# Electronics_Sensor_Modules.net
KiCad netlist of a schematic drawn in EasyEDA
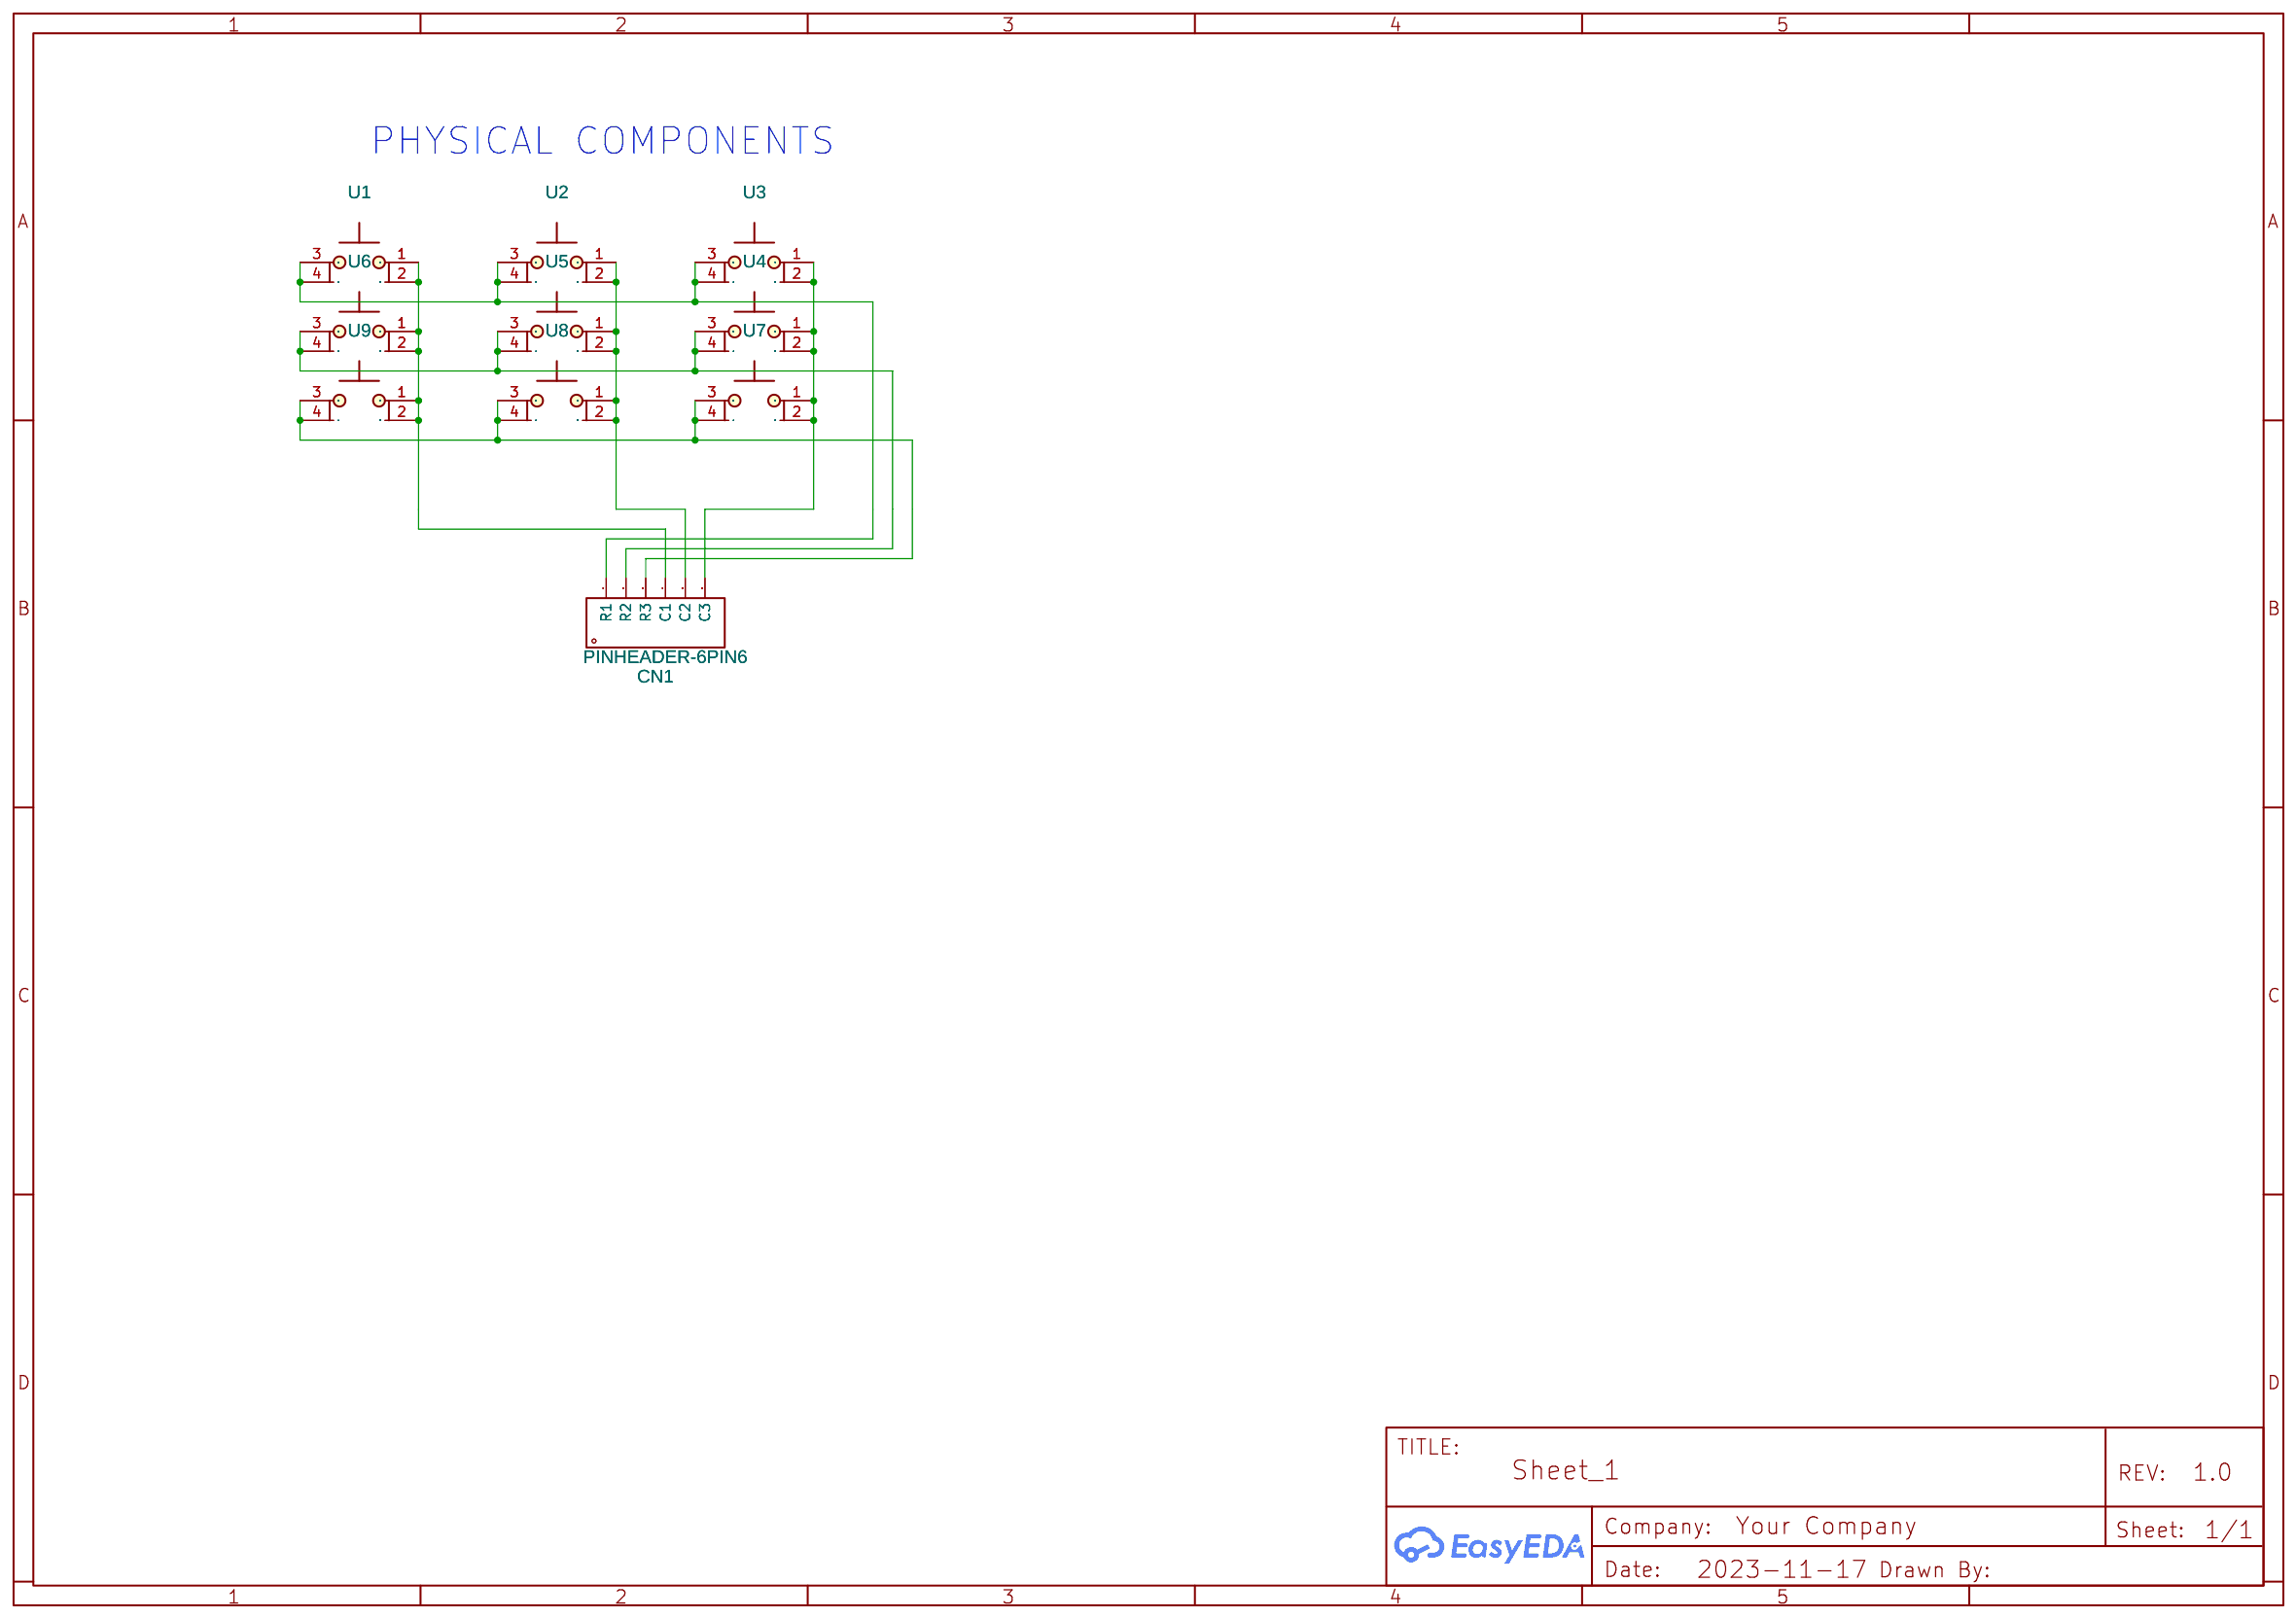
[diagram p0: 3x3 KeyPad]
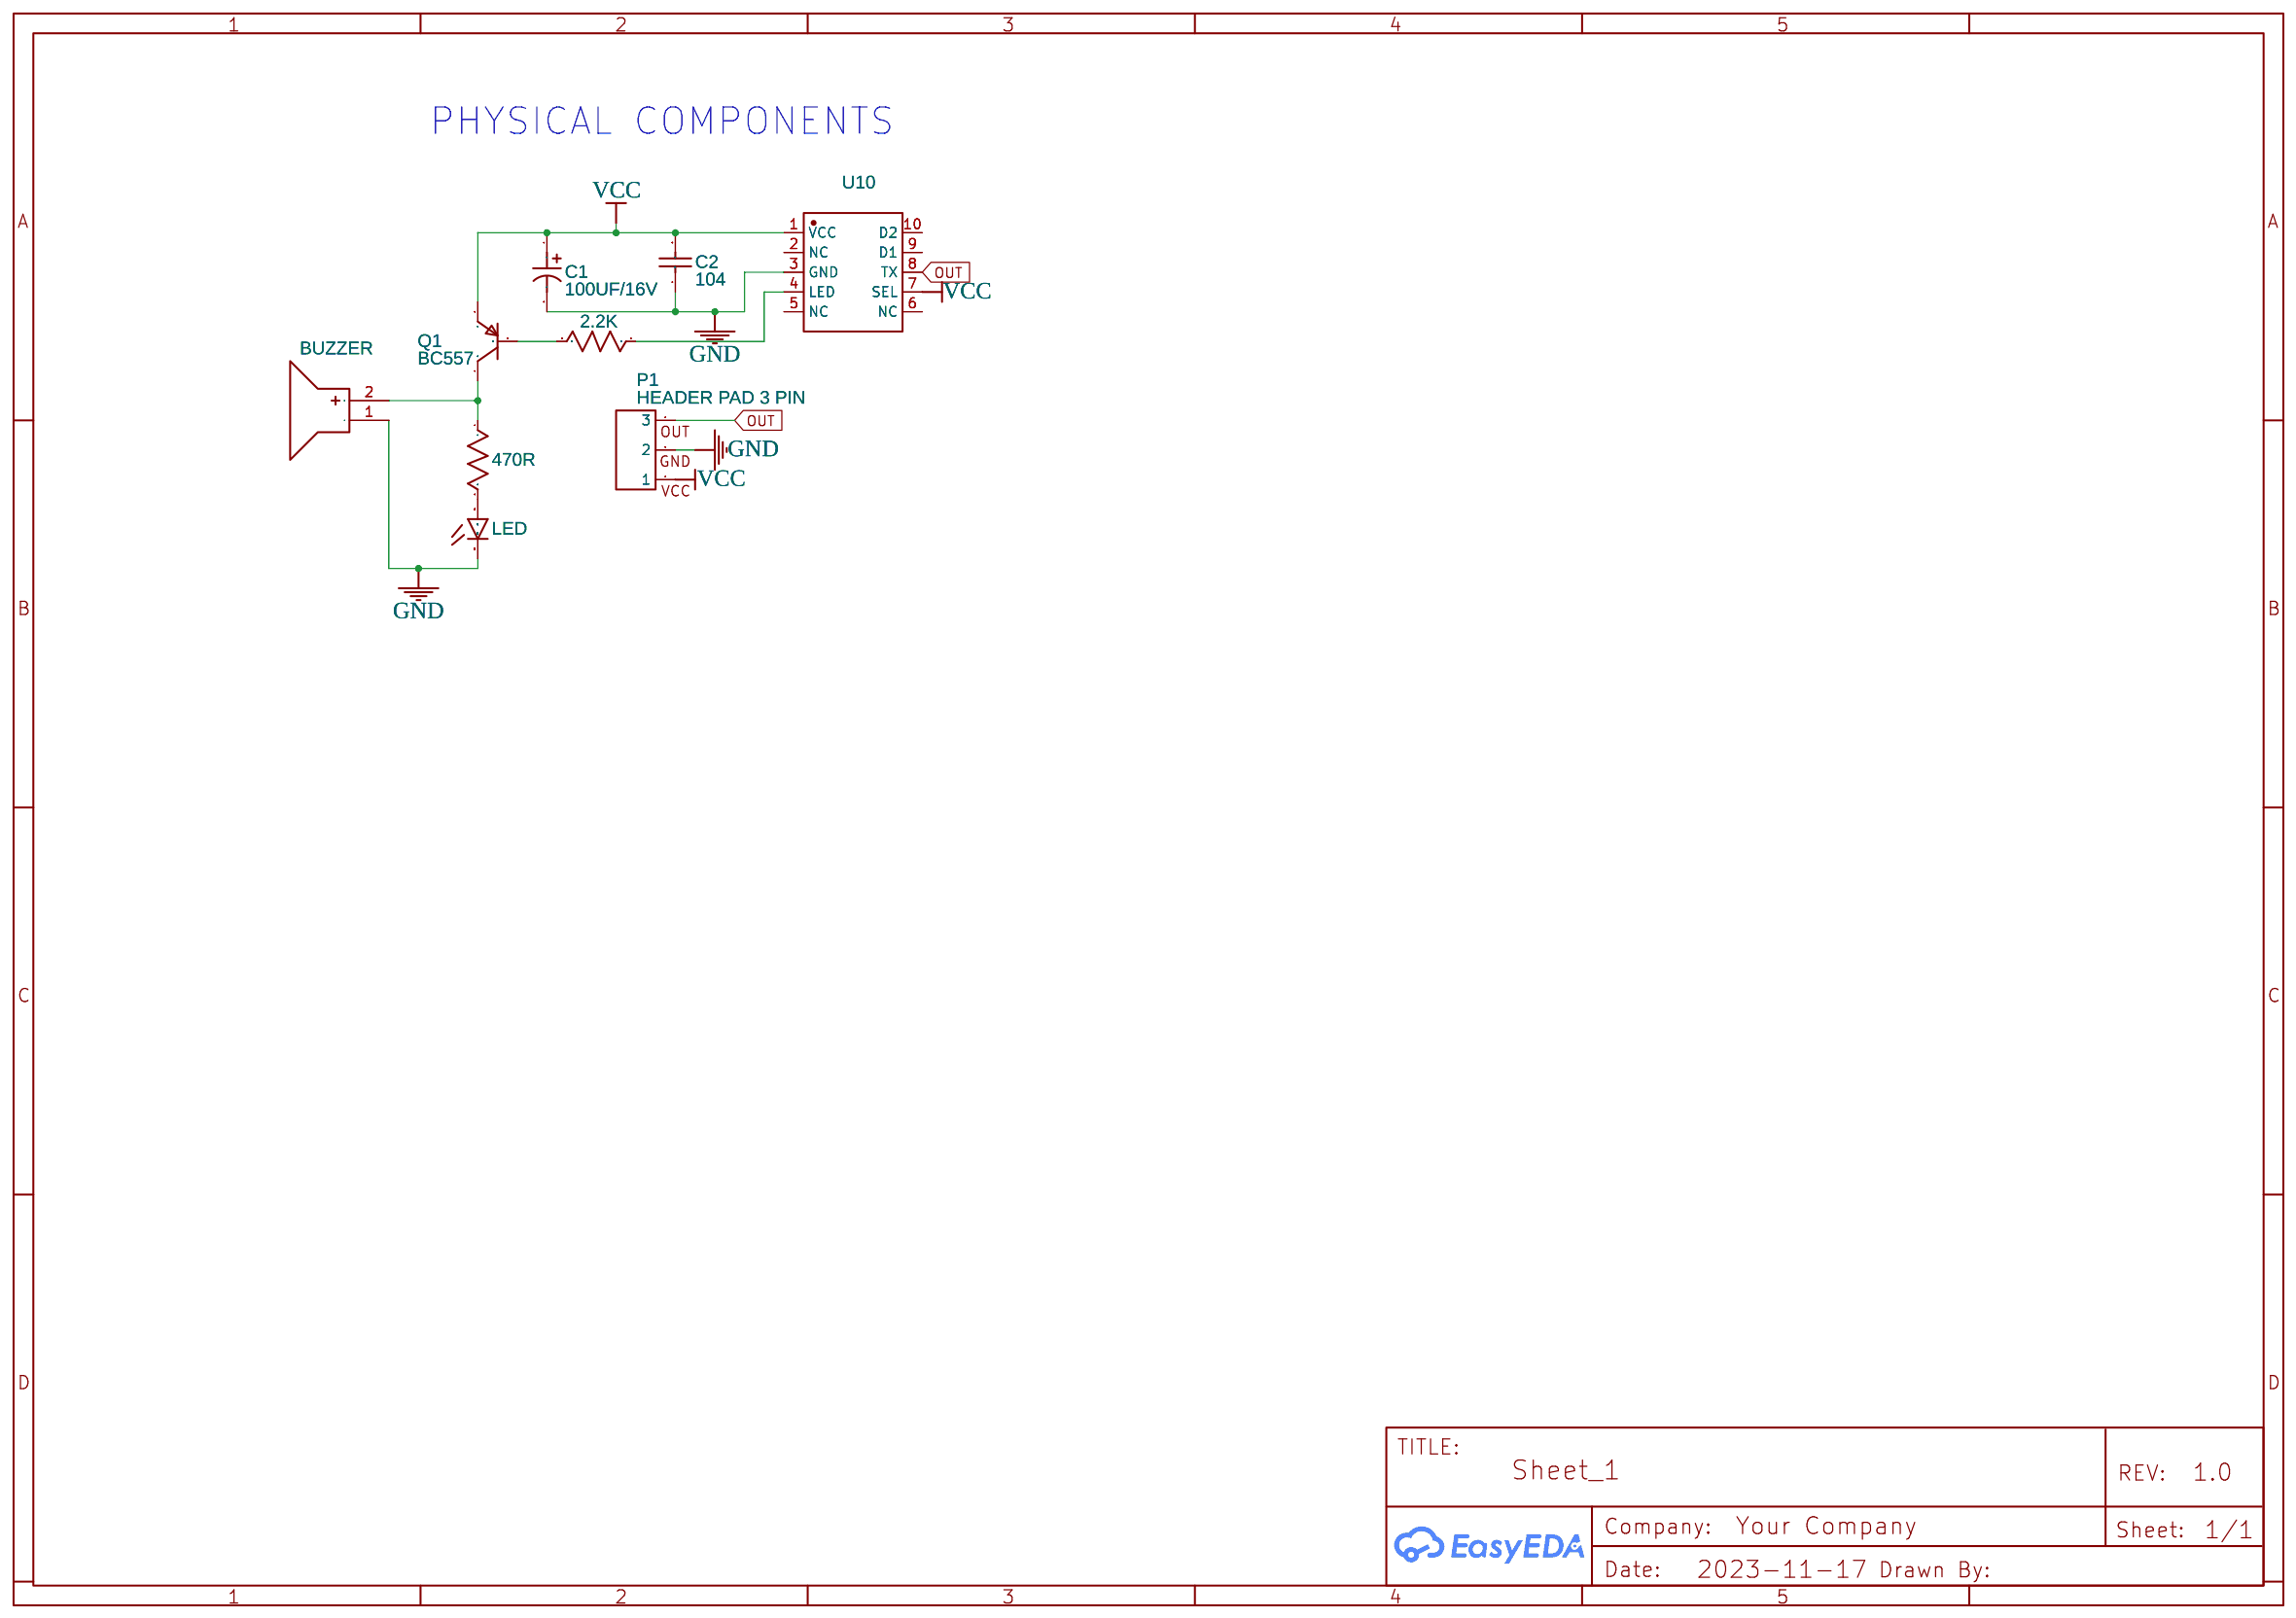
[diagram p1: EM-18 Module]
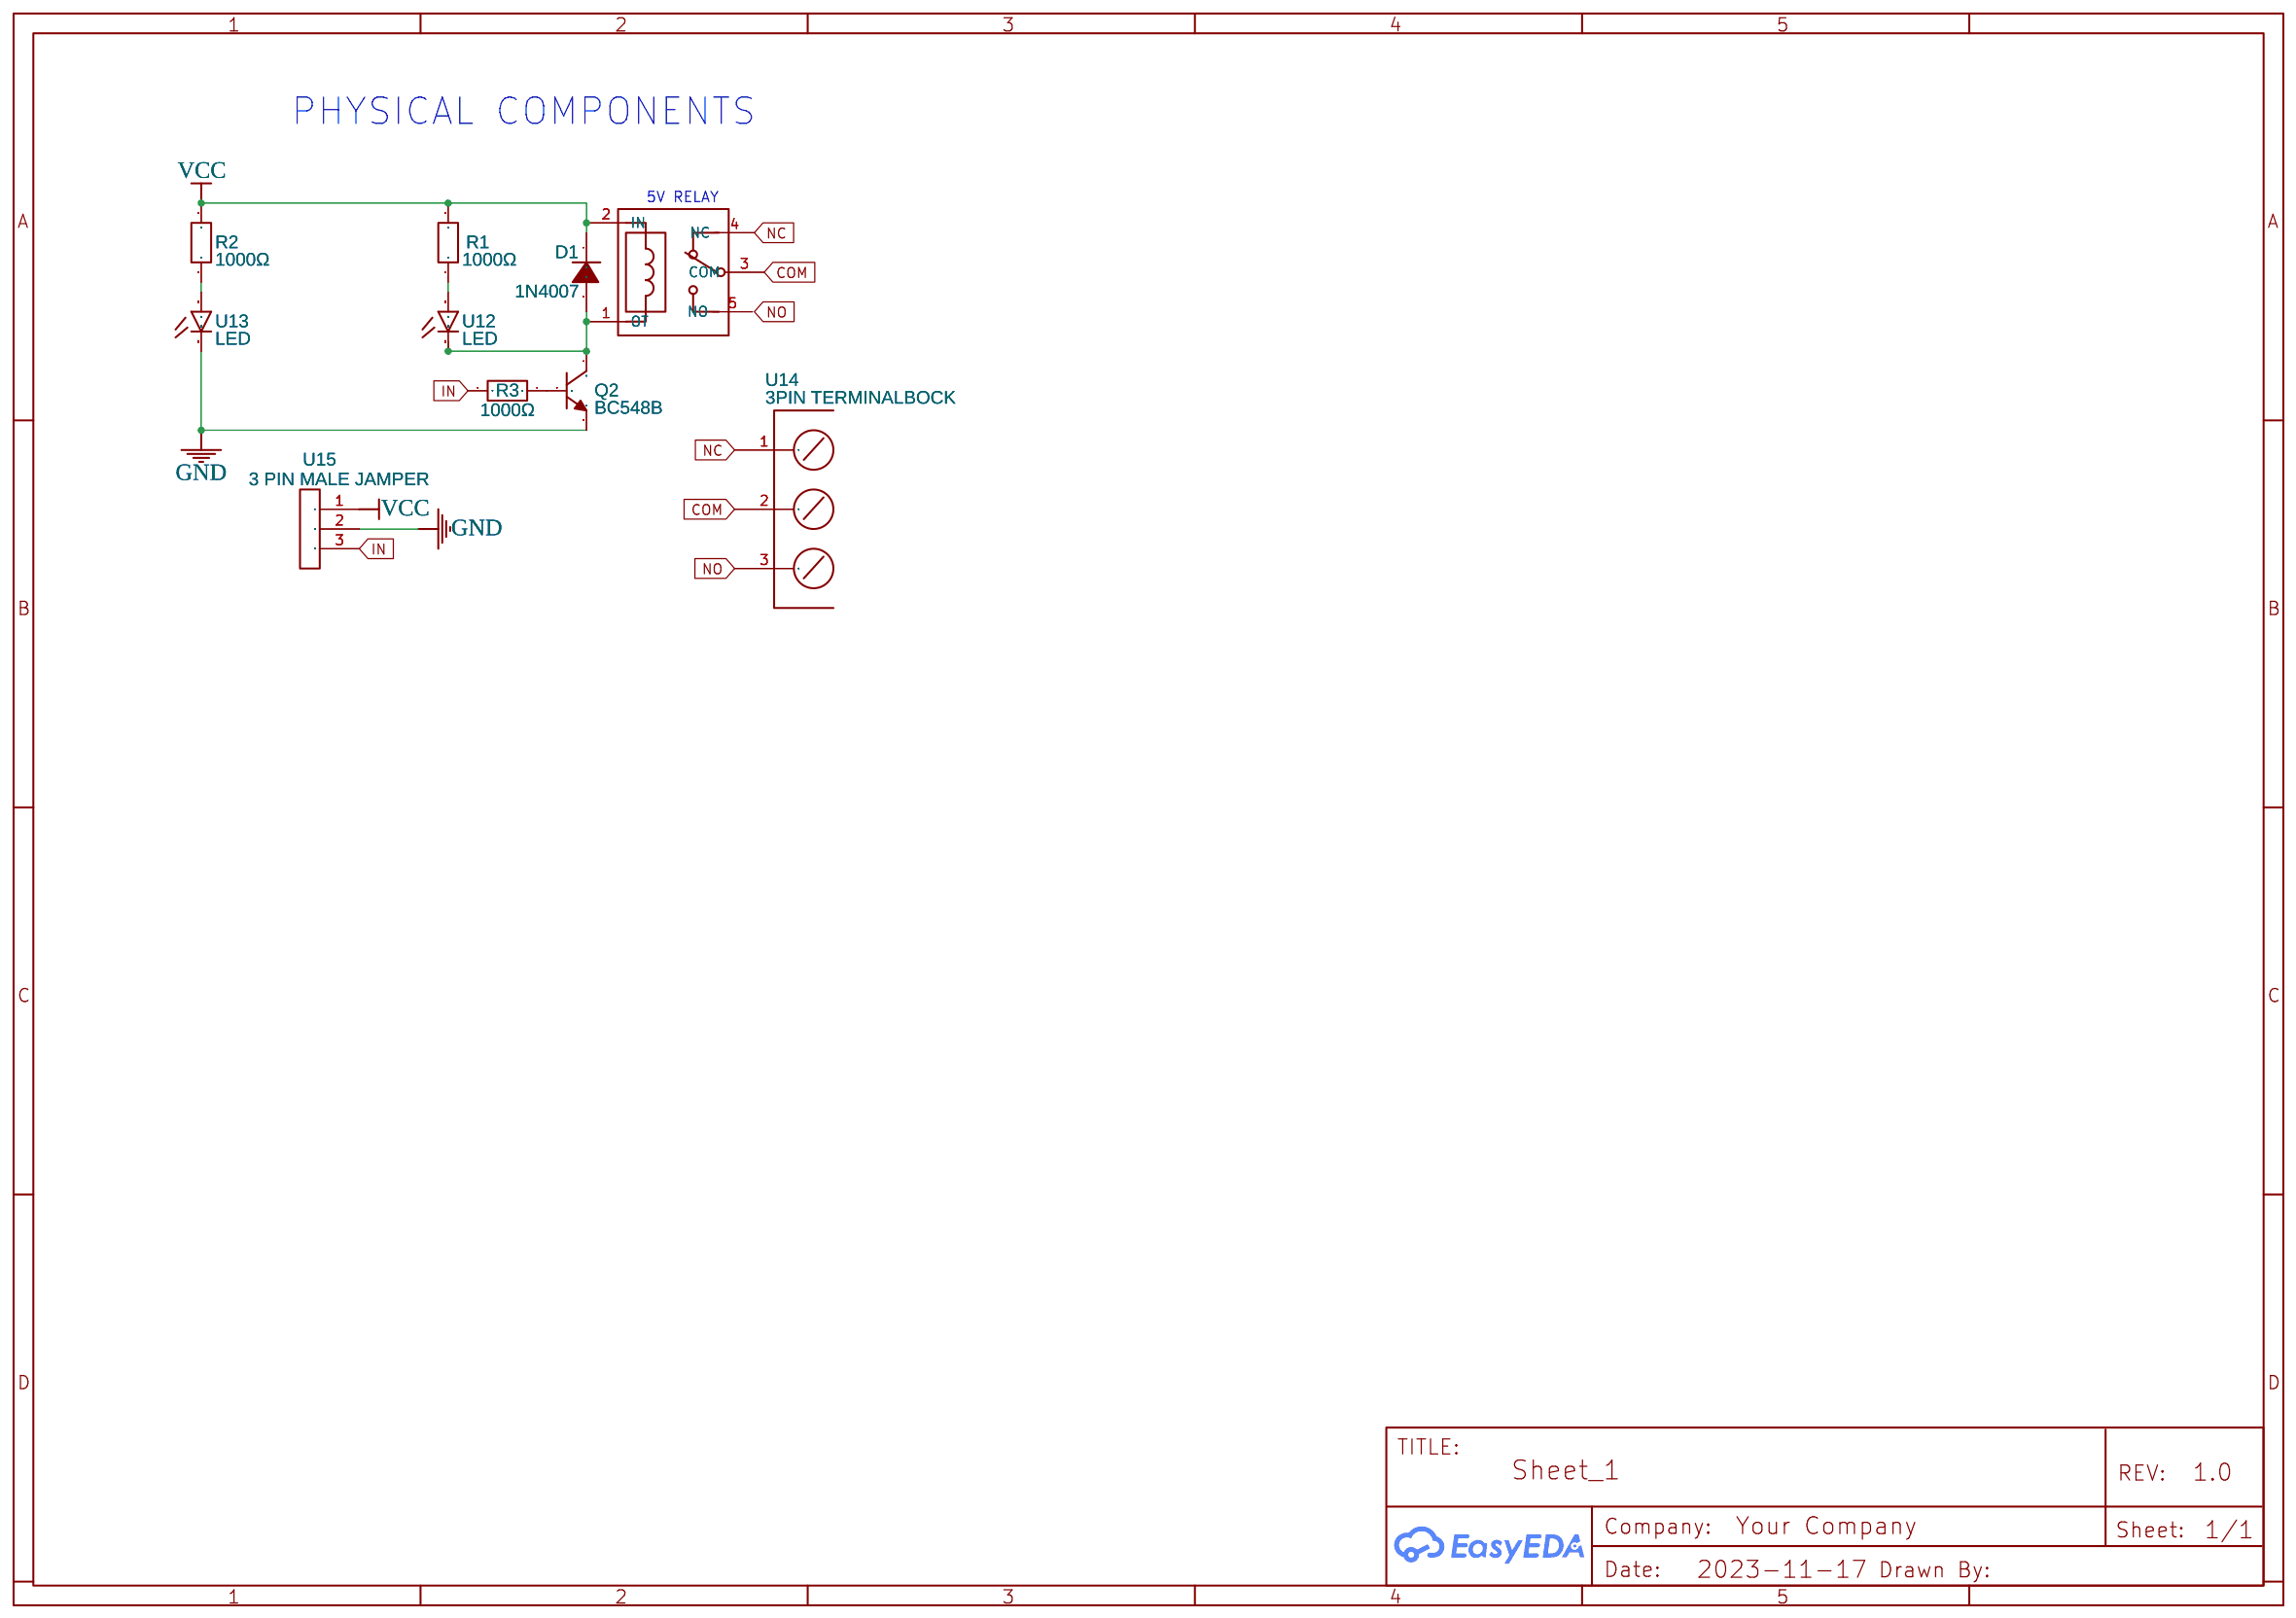
[diagram p2: Relay Module]
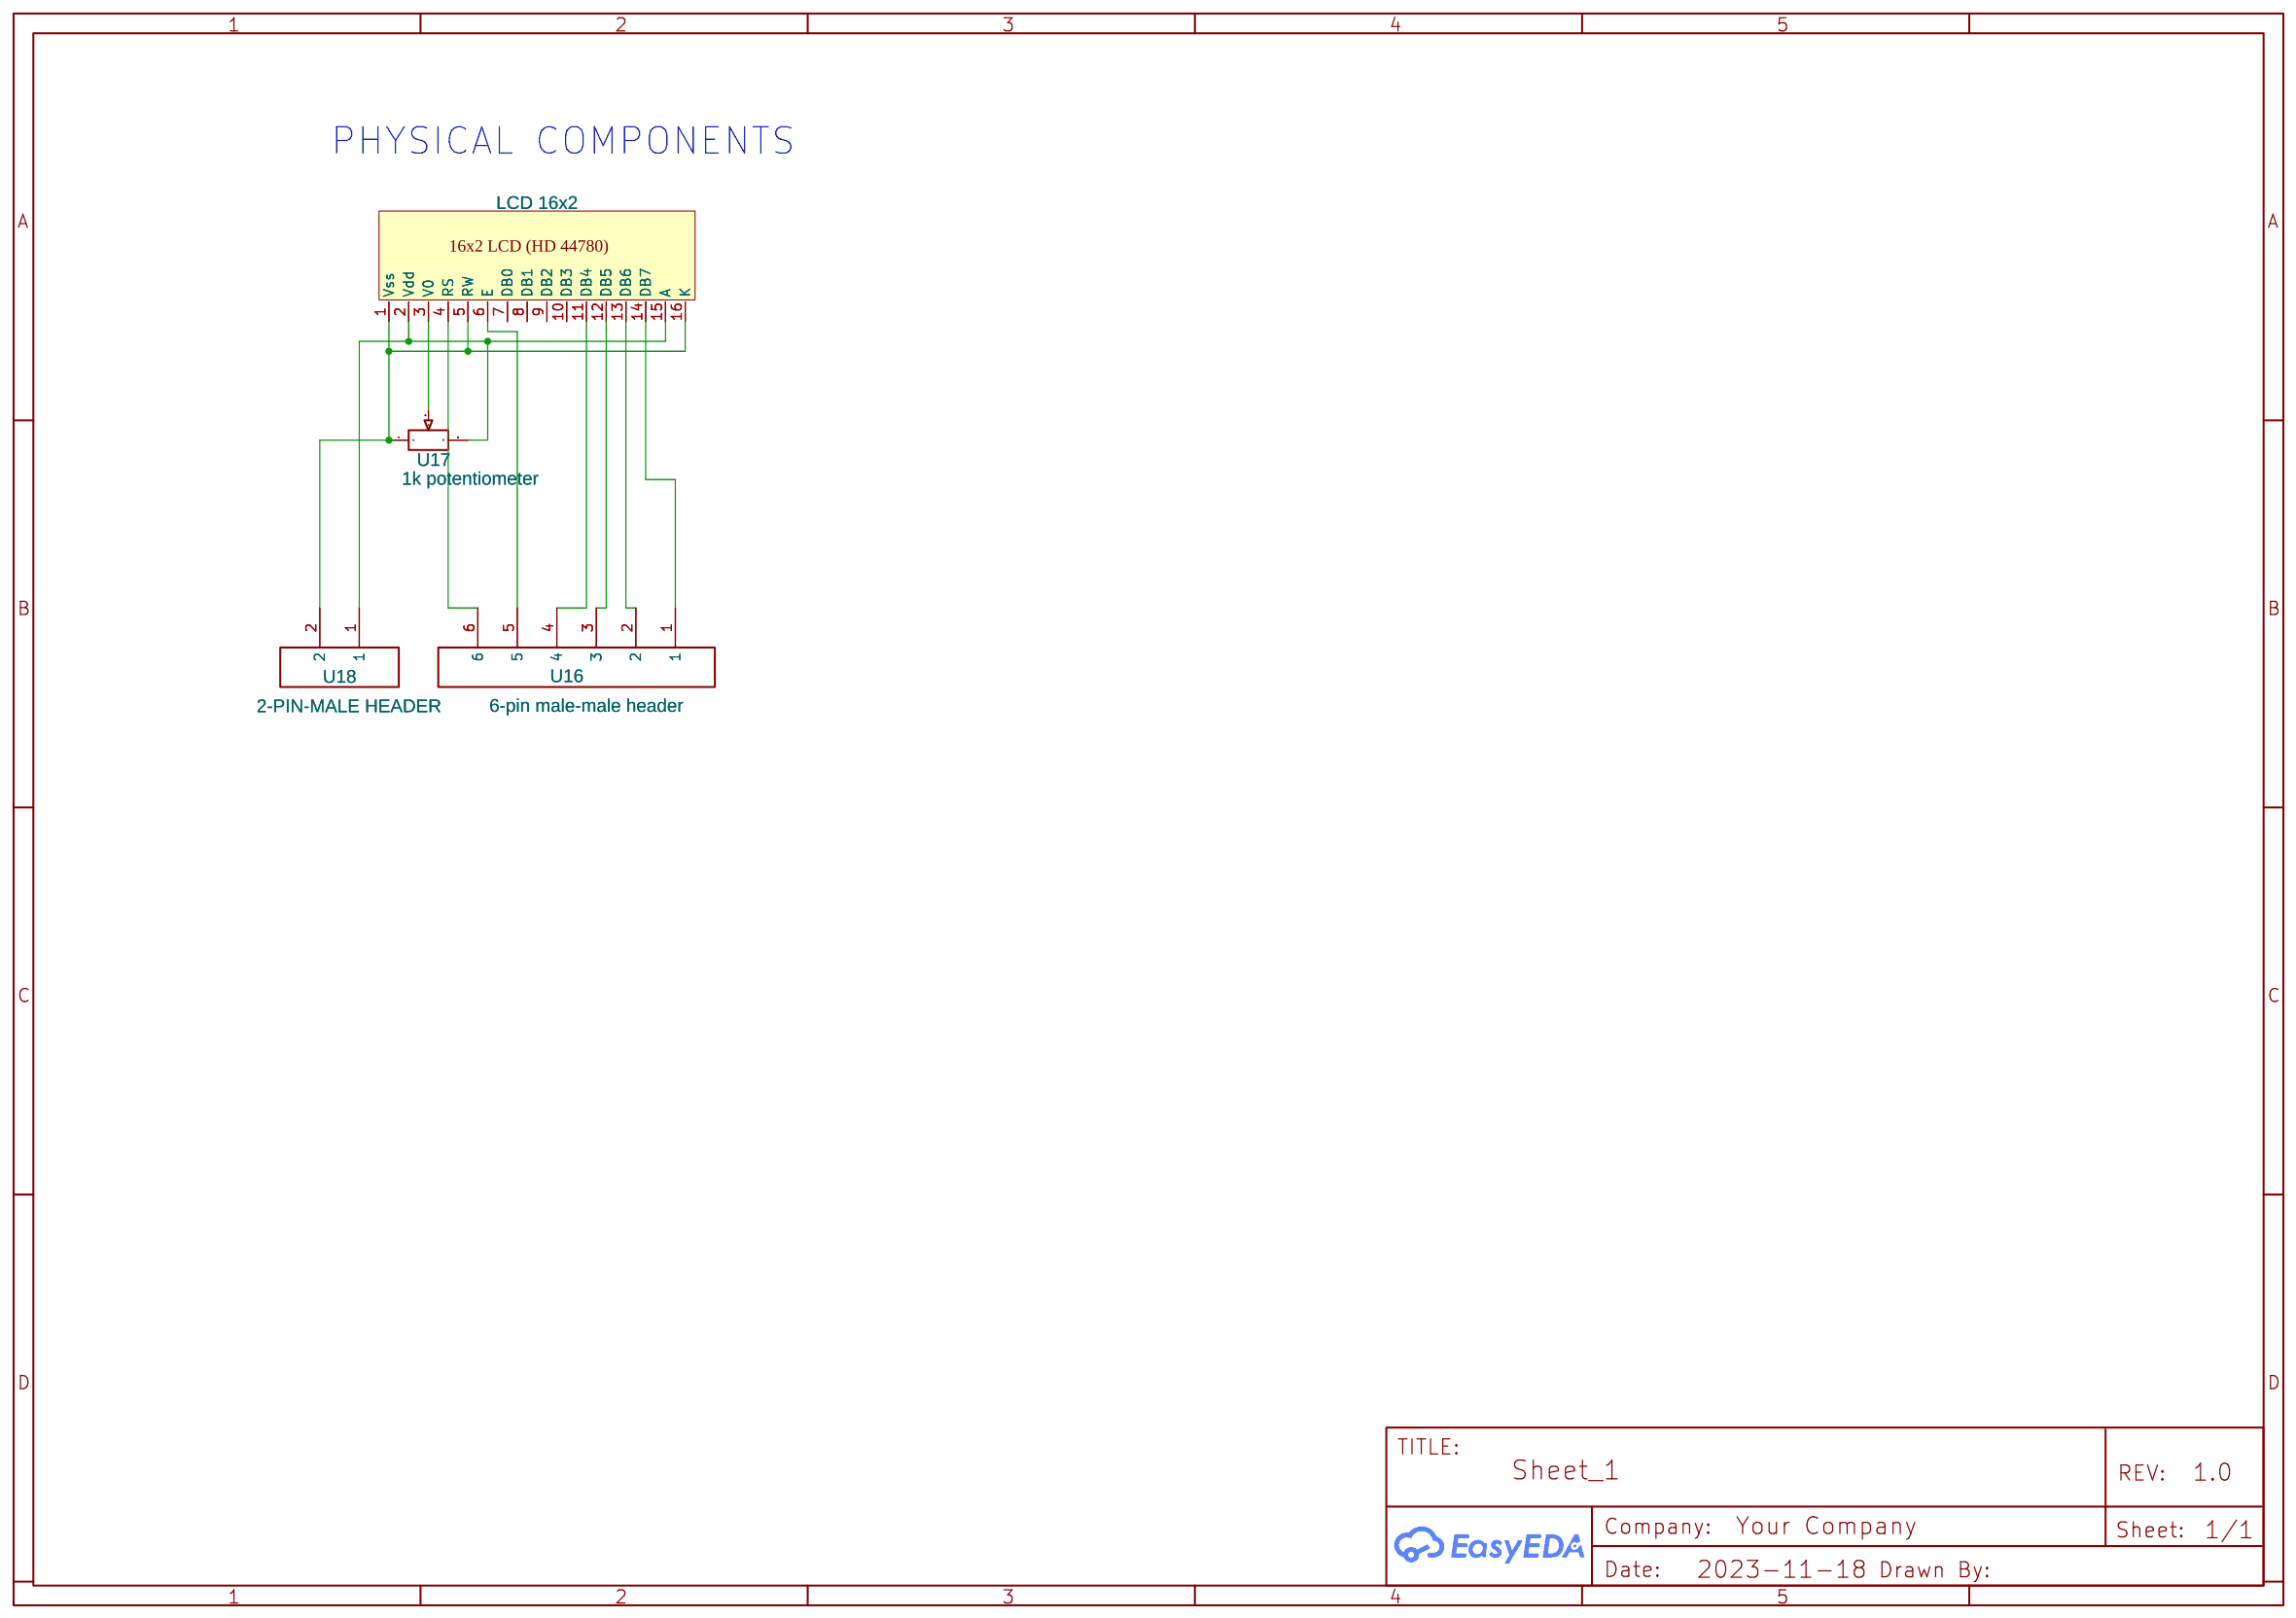
[diagram p3: 16x2 LCD Display]

(export (version "E")
  (design (tool "Eeschema 10.0.6"))
  (components
    (comp (ref "CN1") (value "PINHEADER-6PIN6") (libsource (lib "") (part "PINHEADER-6PIN6")))
    (comp (ref "U1") (value "~") (libsource (lib "") (part "ESO_SPST_Momentary")))
    (comp (ref "U2") (value "~") (libsource (lib "") (part "ESO_SPST_Momentary")))
    (comp (ref "U3") (value "~") (libsource (lib "") (part "ESO_SPST_Momentary")))
    (comp (ref "U4") (value "~") (libsource (lib "") (part "ESO_SPST_Momentary")))
    (comp (ref "U5") (value "~") (libsource (lib "") (part "ESO_SPST_Momentary")))
    (comp (ref "U6") (value "~") (libsource (lib "") (part "ESO_SPST_Momentary")))
    (comp (ref "U7") (value "~") (libsource (lib "") (part "ESO_SPST_Momentary")))
    (comp (ref "U8") (value "~") (libsource (lib "") (part "ESO_SPST_Momentary")))
    (comp (ref "U9") (value "~") (libsource (lib "") (part "ESO_SPST_Momentary")))
    (comp (ref "2.2K")
      (value "~")
      (fields (field (name "Manufacturer") "Huaxing Mechanical-Elec."))
      (libsource (lib "") (part "1/4W-2.2KΩ±1%"))
    )
    (comp (ref "470R")
      (value "~")
      (fields (field (name "Manufacturer") "Huaxing Mechanical-Elec."))
      (libsource (lib "") (part "1/4W-2.2KΩ±1%_1"))
    )
    (comp (ref "BUZZER1")
      (value "BUZZER")
      (fields (field (name "Manufacturer Part") "buzzer"))
      (libsource (lib "") (part "BUZZER"))
    )
    (comp (ref "C1")
      (value "100UF/16V")
      (fields (field (name "Manufacturer Part") "100uF/16V"))
      (libsource (lib "") (part "100UF/16V"))
    )
    (comp (ref "C2")
      (value "104")
      (fields
        (field (name "Manufacturer Part") "Suppression Capacitor222M/250V")
        (field (name "Manufacturer") "ReliaPro")
      )
      (libsource (lib "") (part "104nf"))
    )
    (comp (ref "LED") (value "~") (libsource (lib "") (part "-LED")))
    (comp (ref "P1")
      (value "HEADER PAD 3 PIN")
      (fields
        (field (name "Manufacturer Part") "Female headerHDR1X8-2.54")
        (field (name "Manufacturer") "BOOMELE")
      )
      (libsource (lib "") (part "HEADER PAD 3 PIN"))
    )
    (comp (ref "Q1")
      (value "BC557")
      (fields (field (name "Manufacturer") "CJ(江苏长电/长晶)"))
      (libsource (lib "") (part "BC557"))
    )
    (comp (ref "U10") (value "~") (libsource (lib "") (part "EM-18")))
    (comp (ref "D1")
      (value "1N4007")
      (fields (field (name "Manufacturer") "ST(先科)"))
      (libsource (lib "") (part "1N4007"))
    )
    (comp (ref "Q2")
      (value "BC548B")
      (fields (field (name "Manufacturer Part") "BC548") (field (name "Manufacturer") "CJ(江苏长电/长晶)"))
      (libsource (lib "") (part "BC548B"))
    )
    (comp (ref "R1") (value "1000Ω") (libsource (lib "") (part "330Ω RESISTANCE_1")))
    (comp (ref "R2") (value "1000Ω") (libsource (lib "") (part "330Ω RESISTANCE_1")))
    (comp (ref "R3") (value "1000Ω") (libsource (lib "") (part "330Ω RESISTANCE")))
    (comp (ref "U11")
      (value "~")
      (fields (field (name "Manufacturer Part") "SRD-05VDC-SL-C") (field (name "Manufacturer") "松乐"))
      (libsource (lib "") (part "SRD-05VDC-SL-C"))
    )
    (comp (ref "U12") (value "LED") (libsource (lib "") (part "-LED")))
    (comp (ref "U13") (value "LED") (libsource (lib "") (part "-LED")))
    (comp (ref "U14") (value "3PIN TERMINALBOCK") (libsource (lib "") (part "3PIN TERMINALBOCK")))
    (comp (ref "U15")
      (value "3 PIN MALE JAMPER")
      (fields (field (name "Manufacturer Part") "1x3 pin header") (field (name "Manufacturer") "NA"))
      (libsource (lib "") (part "3 PIN MALE JAMPER"))
    )
    (comp (ref "LCD1") (value "LCD 16x2") (libsource (lib "") (part "LCD 16x2")))
    (comp (ref "U16")
      (value "6-pin male-male header")
      (fields (field (name "Manufacturer Part") "87224-5") (field (name "Manufacturer") "TE Connectivity"))
      (libsource (lib "") (part "6-pin male-male header"))
    )
    (comp (ref "U17") (value "1k potentiometer") (libsource (lib "") (part "Pot_blue")))
    (comp (ref "U18")
      (value "2-PIN-MALE HEADER")
      (fields (field (name "Manufacturer Part") "87224-5") (field (name "Manufacturer") "TE Connectivity"))
      (libsource (lib "") (part "2-PIN-MALE HEADER"))
    )
  )
  (nets
    (net (code "1") (name "COM") (class "Default")
      (node (ref "U11") (pin "3") (pinfunction "COM_3") (pintype "unspecified"))
      (node (ref "U14") (pin "2") (pinfunction "2_2") (pintype "unspecified"))
    )
    (net (code "2") (name "GND") (class "Default")
      (node (ref "BUZZER1") (pin "1") (pinfunction "-_1") (pintype "unspecified"))
      (node (ref "C1") (pin "2") (pinfunction "2_2") (pintype "input"))
      (node (ref "C2") (pin "1") (pinfunction "1_1") (pintype "input"))
      (node (ref "LED") (pin "CATHODE") (pinfunction "CATHODE_CATHODE") (pintype "unspecified"))
      (node (ref "P1") (pin "2") (pinfunction "2_2") (pintype "input"))
      (node (ref "Q2") (pin "3") (pinfunction "E_3") (pintype "unspecified"))
      (node (ref "U10") (pin "3") (pinfunction "GND_3") (pintype "unspecified"))
      (node (ref "U13") (pin "CATHODE") (pinfunction "CATHODE_CATHODE") (pintype "unspecified"))
      (node (ref "U15") (pin "2") (pinfunction "2_2") (pintype "unspecified"))
    )
    (net (code "3") (name "IN") (class "Default")
      (node (ref "R3") (pin "2") (pinfunction "2_2") (pintype "unspecified"))
      (node (ref "U15") (pin "3") (pinfunction "3_3") (pintype "unspecified"))
    )
    (net (code "4") (name "NC") (class "Default")
      (node (ref "U11") (pin "4") (pinfunction "NC_4") (pintype "unspecified"))
      (node (ref "U14") (pin "1") (pinfunction "1_1") (pintype "unspecified"))
    )
    (net (code "5") (name "NO") (class "Default")
      (node (ref "U14") (pin "3") (pinfunction "3_3") (pintype "unspecified"))
    )
    (net (code "6") (name "Net-(470R-Pad2)") (class "Default")
      (node (ref "470R") (pin "2") (pinfunction "2_2") (pintype "unspecified"))
      (node (ref "LED") (pin "ANODE") (pinfunction "ANODE_ANODE") (pintype "unspecified"))
    )
    (net (code "7") (name "Net-(BUZZER1-+)") (class "Default")
      (node (ref "470R") (pin "1") (pinfunction "1_1") (pintype "unspecified"))
      (node (ref "BUZZER1") (pin "2") (pinfunction "+_2") (pintype "unspecified"))
      (node (ref "Q1") (pin "1") (pinfunction "C_1") (pintype "unspecified"))
    )
    (net (code "8") (name "Net-(CN1-C1)") (class "Default")
      (node (ref "CN1") (pin "4") (pinfunction "C1_4") (pintype "input"))
      (node (ref "U1") (pin "1") (pinfunction "1_1") (pintype "unspecified"))
      (node (ref "U1") (pin "2") (pinfunction "2_2") (pintype "unspecified"))
      (node (ref "U6") (pin "1") (pinfunction "1_1") (pintype "unspecified"))
      (node (ref "U6") (pin "2") (pinfunction "2_2") (pintype "unspecified"))
      (node (ref "U9") (pin "1") (pinfunction "1_1") (pintype "unspecified"))
      (node (ref "U9") (pin "2") (pinfunction "2_2") (pintype "unspecified"))
    )
    (net (code "9") (name "Net-(CN1-C2)") (class "Default")
      (node (ref "CN1") (pin "5") (pinfunction "C2_5") (pintype "input"))
      (node (ref "U2") (pin "1") (pinfunction "1_1") (pintype "unspecified"))
      (node (ref "U2") (pin "2") (pinfunction "2_2") (pintype "unspecified"))
      (node (ref "U5") (pin "1") (pinfunction "1_1") (pintype "unspecified"))
      (node (ref "U5") (pin "2") (pinfunction "2_2") (pintype "unspecified"))
      (node (ref "U8") (pin "1") (pinfunction "1_1") (pintype "unspecified"))
      (node (ref "U8") (pin "2") (pinfunction "2_2") (pintype "unspecified"))
    )
    (net (code "10") (name "Net-(CN1-C3)") (class "Default")
      (node (ref "CN1") (pin "6") (pinfunction "C3_6") (pintype "input"))
      (node (ref "U3") (pin "1") (pinfunction "1_1") (pintype "unspecified"))
      (node (ref "U3") (pin "2") (pinfunction "2_2") (pintype "unspecified"))
      (node (ref "U4") (pin "1") (pinfunction "1_1") (pintype "unspecified"))
      (node (ref "U4") (pin "2") (pinfunction "2_2") (pintype "unspecified"))
      (node (ref "U7") (pin "1") (pinfunction "1_1") (pintype "unspecified"))
      (node (ref "U7") (pin "2") (pinfunction "2_2") (pintype "unspecified"))
    )
    (net (code "11") (name "Net-(CN1-R1)") (class "Default")
      (node (ref "CN1") (pin "1") (pinfunction "R1_1") (pintype "input"))
      (node (ref "U1") (pin "3") (pinfunction "3_3") (pintype "unspecified"))
      (node (ref "U1") (pin "4") (pinfunction "4_4") (pintype "unspecified"))
      (node (ref "U2") (pin "3") (pinfunction "3_3") (pintype "unspecified"))
      (node (ref "U2") (pin "4") (pinfunction "4_4") (pintype "unspecified"))
      (node (ref "U3") (pin "3") (pinfunction "3_3") (pintype "unspecified"))
      (node (ref "U3") (pin "4") (pinfunction "4_4") (pintype "unspecified"))
    )
    (net (code "12") (name "Net-(CN1-R2)") (class "Default")
      (node (ref "CN1") (pin "2") (pinfunction "R2_2") (pintype "input"))
      (node (ref "U4") (pin "3") (pinfunction "3_3") (pintype "unspecified"))
      (node (ref "U4") (pin "4") (pinfunction "4_4") (pintype "unspecified"))
      (node (ref "U5") (pin "3") (pinfunction "3_3") (pintype "unspecified"))
      (node (ref "U5") (pin "4") (pinfunction "4_4") (pintype "unspecified"))
      (node (ref "U6") (pin "3") (pinfunction "3_3") (pintype "unspecified"))
      (node (ref "U6") (pin "4") (pinfunction "4_4") (pintype "unspecified"))
    )
    (net (code "13") (name "Net-(CN1-R3)") (class "Default")
      (node (ref "CN1") (pin "3") (pinfunction "R3_3") (pintype "input"))
      (node (ref "U7") (pin "3") (pinfunction "3_3") (pintype "unspecified"))
      (node (ref "U7") (pin "4") (pinfunction "4_4") (pintype "unspecified"))
      (node (ref "U8") (pin "3") (pinfunction "3_3") (pintype "unspecified"))
      (node (ref "U8") (pin "4") (pinfunction "4_4") (pintype "unspecified"))
      (node (ref "U9") (pin "3") (pinfunction "3_3") (pintype "unspecified"))
      (node (ref "U9") (pin "4") (pinfunction "4_4") (pintype "unspecified"))
    )
    (net (code "14") (name "Net-(D1-A)") (class "Default")
      (node (ref "D1") (pin "2") (pinfunction "A_2") (pintype "unspecified"))
      (node (ref "Q2") (pin "1") (pinfunction "C_1") (pintype "unspecified"))
      (node (ref "U11") (pin "1") (pinfunction "OT_1") (pintype "unspecified"))
      (node (ref "U12") (pin "CATHODE") (pinfunction "CATHODE_CATHODE") (pintype "unspecified"))
    )
    (net (code "15") (name "Net-(LCD1-A)") (class "Default")
      (node (ref "LCD1") (pin "15") (pinfunction "A_15") (pintype "unspecified"))
      (node (ref "LCD1") (pin "2") (pinfunction "Vdd_2") (pintype "unspecified"))
      (node (ref "U17") (pin "3") (pinfunction "2_3") (pintype "input"))
      (node (ref "U18") (pin "1") (pinfunction "1_1") (pintype "unspecified"))
    )
    (net (code "16") (name "Net-(LCD1-DB4)") (class "Default")
      (node (ref "LCD1") (pin "11") (pinfunction "DB4_11") (pintype "unspecified"))
      (node (ref "U16") (pin "4") (pinfunction "4_4") (pintype "unspecified"))
    )
    (net (code "17") (name "Net-(LCD1-DB5)") (class "Default")
      (node (ref "LCD1") (pin "12") (pinfunction "DB5_12") (pintype "unspecified"))
      (node (ref "U16") (pin "3") (pinfunction "3_3") (pintype "unspecified"))
    )
    (net (code "18") (name "Net-(LCD1-DB6)") (class "Default")
      (node (ref "LCD1") (pin "13") (pinfunction "DB6_13") (pintype "unspecified"))
      (node (ref "U16") (pin "2") (pinfunction "2_2") (pintype "unspecified"))
    )
    (net (code "19") (name "Net-(LCD1-DB7)") (class "Default")
      (node (ref "LCD1") (pin "14") (pinfunction "DB7_14") (pintype "unspecified"))
      (node (ref "U16") (pin "1") (pinfunction "1_1") (pintype "unspecified"))
    )
    (net (code "20") (name "Net-(LCD1-E)") (class "Default")
      (node (ref "LCD1") (pin "6") (pinfunction "E_6") (pintype "unspecified"))
      (node (ref "U16") (pin "5") (pinfunction "5_5") (pintype "unspecified"))
    )
    (net (code "21") (name "Net-(LCD1-K)") (class "Default")
      (node (ref "LCD1") (pin "1") (pinfunction "Vss_1") (pintype "unspecified"))
      (node (ref "LCD1") (pin "16") (pinfunction "K_16") (pintype "unspecified"))
      (node (ref "LCD1") (pin "5") (pinfunction "RW_5") (pintype "unspecified"))
      (node (ref "U17") (pin "1") (pinfunction "1_1") (pintype "input"))
      (node (ref "U18") (pin "2") (pinfunction "2_2") (pintype "unspecified"))
    )
    (net (code "22") (name "Net-(LCD1-RS)") (class "Default")
      (node (ref "LCD1") (pin "4") (pinfunction "RS_4") (pintype "unspecified"))
      (node (ref "U16") (pin "6") (pinfunction "6_6") (pintype "unspecified"))
    )
    (net (code "23") (name "Net-(LCD1-V0)") (class "Default")
      (node (ref "LCD1") (pin "3") (pinfunction "V0_3") (pintype "unspecified"))
      (node (ref "U17") (pin "2") (pinfunction "3_2") (pintype "input"))
    )
    (net (code "24") (name "Net-(Q1-B)") (class "Default")
      (node (ref "2.2K") (pin "2") (pinfunction "2_2") (pintype "unspecified"))
      (node (ref "Q1") (pin "2") (pinfunction "B_2") (pintype "unspecified"))
    )
    (net (code "25") (name "Net-(Q2-B)") (class "Default")
      (node (ref "Q2") (pin "2") (pinfunction "B_2") (pintype "unspecified"))
      (node (ref "R3") (pin "1") (pinfunction "1_1") (pintype "unspecified"))
    )
    (net (code "26") (name "Net-(R1-Pad1)") (class "Default")
      (node (ref "R1") (pin "1") (pinfunction "1_1") (pintype "unspecified"))
      (node (ref "U12") (pin "ANODE") (pinfunction "ANODE_ANODE") (pintype "unspecified"))
    )
    (net (code "27") (name "Net-(R2-Pad1)") (class "Default")
      (node (ref "R2") (pin "1") (pinfunction "1_1") (pintype "unspecified"))
      (node (ref "U13") (pin "ANODE") (pinfunction "ANODE_ANODE") (pintype "unspecified"))
    )
    (net (code "28") (name "Net-(U10-LED)") (class "Default")
      (node (ref "2.2K") (pin "1") (pinfunction "1_1") (pintype "unspecified"))
      (node (ref "U10") (pin "4") (pinfunction "LED_4") (pintype "unspecified"))
    )
    (net (code "29") (name "OUT") (class "Default")
      (node (ref "P1") (pin "3") (pinfunction "3_3") (pintype "input"))
      (node (ref "U10") (pin "8") (pinfunction "TX_8") (pintype "unspecified"))
    )
    (net (code "30") (name "VCC") (class "Default")
      (node (ref "C1") (pin "1") (pinfunction "1_1") (pintype "input"))
      (node (ref "C2") (pin "2") (pinfunction "2_2") (pintype "input"))
      (node (ref "D1") (pin "1") (pinfunction "K_1") (pintype "unspecified"))
      (node (ref "P1") (pin "1") (pinfunction "1_1") (pintype "input"))
      (node (ref "Q1") (pin "3") (pinfunction "E_3") (pintype "unspecified"))
      (node (ref "R1") (pin "2") (pinfunction "2_2") (pintype "unspecified"))
      (node (ref "R2") (pin "2") (pinfunction "2_2") (pintype "unspecified"))
      (node (ref "U10") (pin "1") (pinfunction "VCC_1") (pintype "unspecified"))
      (node (ref "U10") (pin "7") (pinfunction "SEL_7") (pintype "unspecified"))
      (node (ref "U11") (pin "2") (pinfunction "IN_2") (pintype "unspecified"))
      (node (ref "U15") (pin "1") (pinfunction "1_1") (pintype "unspecified"))
    )
    (net (code "31") (name "unconnected-(LCD1-DB0-Pad7)") (class "Default")
      (node (ref "LCD1") (pin "7") (pinfunction "DB0_7") (pintype "unspecified"))
    )
    (net (code "32") (name "unconnected-(LCD1-DB1-Pad8)") (class "Default")
      (node (ref "LCD1") (pin "8") (pinfunction "DB1_8") (pintype "unspecified"))
    )
    (net (code "33") (name "unconnected-(LCD1-DB2-Pad9)") (class "Default")
      (node (ref "LCD1") (pin "9") (pinfunction "DB2_9") (pintype "unspecified"))
    )
    (net (code "34") (name "unconnected-(LCD1-DB3-Pad10)") (class "Default")
      (node (ref "LCD1") (pin "10") (pinfunction "DB3_10") (pintype "unspecified"))
    )
    (net (code "35") (name "unconnected-(U10-D1-Pad9)") (class "Default")
      (node (ref "U10") (pin "9") (pinfunction "D1_9") (pintype "unspecified"))
    )
    (net (code "36") (name "unconnected-(U10-D2-Pad10)") (class "Default")
      (node (ref "U10") (pin "10") (pinfunction "D2_10") (pintype "unspecified"))
    )
    (net (code "37") (name "unconnected-(U10-NC-Pad2)") (class "Default")
      (node (ref "U10") (pin "2") (pinfunction "NC_2") (pintype "unspecified"))
    )
    (net (code "38") (name "unconnected-(U10-NC-Pad5)") (class "Default")
      (node (ref "U10") (pin "5") (pinfunction "NC_5") (pintype "unspecified"))
    )
    (net (code "39") (name "unconnected-(U10-NC-Pad6)") (class "Default")
      (node (ref "U10") (pin "6") (pinfunction "NC_6") (pintype "unspecified"))
    )
    (net (code "40") (name "unconnected-(U11-NO-Pad5)") (class "Default")
      (node (ref "U11") (pin "5") (pinfunction "NO_5") (pintype "unspecified"))
    )
  )
)
